# 02_Driver.net
KiCad netlist of a schematic drawn in Altium Designer
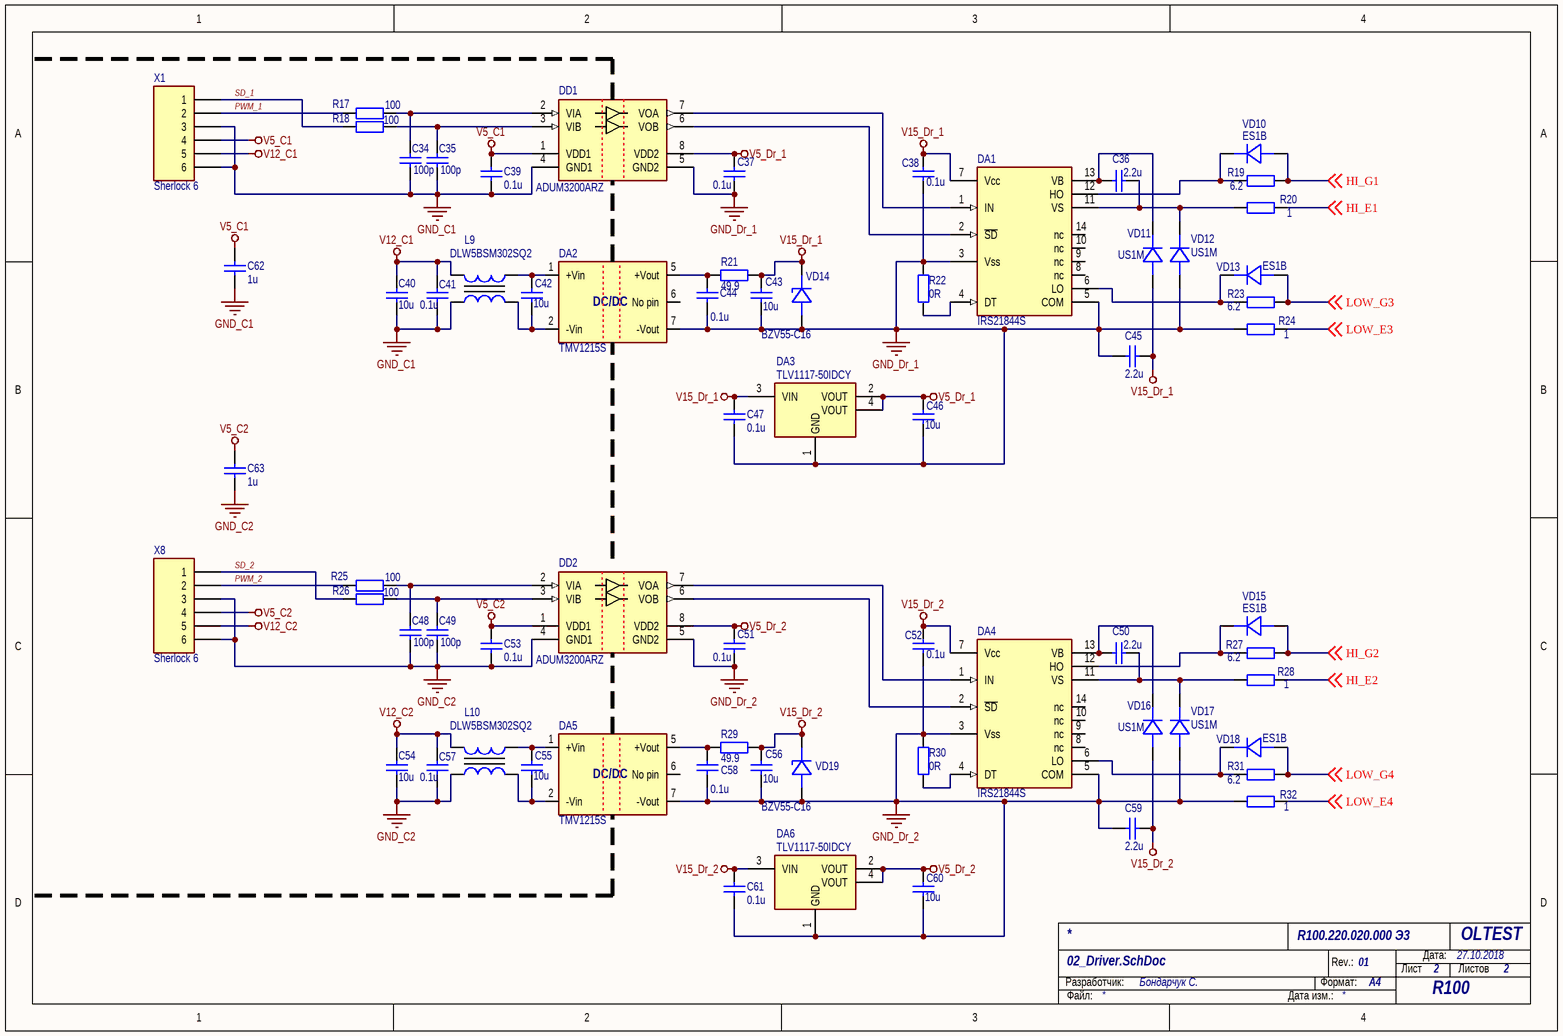
[diagram p0: 02_Driver.SchDoc]

(export (version "E")
  (design (tool "Eeschema 10.0.6"))
  (components
    (comp (ref "C34")
      (value "100p")
      (footprint "mainLib:SMD_C_0603")
      (description "SMD C 0603 MURATA 100V 5% NP0")
      (fields (field (name "PARTNUMBER") "GRM1885C2A101JA01") (field (name "MANUFACTURER") "MURATA"))
      (libsource (lib "mainRCLib") (part "C0603 100p 100V 5%"))
    )
    (comp (ref "C35")
      (value "100p")
      (footprint "mainLib:SMD_C_0603")
      (description "SMD C 0603 MURATA 100V 5% NP0")
      (fields (field (name "PARTNUMBER") "GRM1885C2A101JA01") (field (name "MANUFACTURER") "MURATA"))
      (libsource (lib "mainRCLib") (part "C0603 100p 100V 5%"))
    )
    (comp (ref "C36")
      (value "2.2u")
      (footprint "mainLib:SMD_C_1210")
      (description "SMD C 1210 MURATA 100V 10% X7R")
      (fields (field (name "PARTNUMBER") "GRM32ER72A225KA35L") (field (name "MANUFACTURER") "MURATA"))
      (libsource (lib "mainRCLib") (part "C1210 2.2u 100V 10%"))
    )
    (comp (ref "C37")
      (value "0.1u")
      (footprint "mainLib:SMD_C_0603")
      (description "SMD C 0603 MURATA 50V 10% X7R")
      (fields (field (name "PARTNUMBER") "GRM188R71H104K") (field (name "MANUFACTURER") "MURATA"))
      (libsource (lib "mainRCLib") (part "C0603 0.1u 50V 10%"))
    )
    (comp (ref "C38")
      (value "0.1u")
      (footprint "mainLib:SMD_C_0603")
      (description "SMD C 0603 MURATA 50V 10% X7R")
      (fields (field (name "PARTNUMBER") "GRM188R71H104K") (field (name "MANUFACTURER") "MURATA"))
      (libsource (lib "mainRCLib") (part "C0603 0.1u 50V 10%"))
    )
    (comp (ref "C39")
      (value "0.1u")
      (footprint "mainLib:SMD_C_0603")
      (description "SMD C 0603 MURATA 50V 10% X7R")
      (fields (field (name "PARTNUMBER") "GRM188R71H104K") (field (name "MANUFACTURER") "MURATA"))
      (libsource (lib "mainRCLib") (part "C0603 0.1u 50V 10%"))
    )
    (comp (ref "C40")
      (value "10u")
      (footprint "mainLib:SMD_C_1206")
      (description "SMD C 1206 MURATA 25V 20% X5R")
      (fields (field (name "PARTNUMBER") "GRM31MR61E106M") (field (name "MANUFACTURER") "MURATA"))
      (libsource (lib "mainRCLib") (part "C1206 10u 25V 20%"))
    )
    (comp (ref "C41")
      (value "0.1u")
      (footprint "mainLib:SMD_C_0603")
      (description "SMD C 0603 MURATA 50V 10% X7R")
      (fields (field (name "PARTNUMBER") "GRM188R71H104K") (field (name "MANUFACTURER") "MURATA"))
      (libsource (lib "mainRCLib") (part "C0603 0.1u 50V 10%"))
    )
    (comp (ref "C42")
      (value "10u")
      (footprint "mainLib:SMD_C_1206")
      (description "SMD C 1206 MURATA 25V 20% X5R")
      (fields (field (name "PARTNUMBER") "GRM31MR61E106M") (field (name "MANUFACTURER") "MURATA"))
      (libsource (lib "mainRCLib") (part "C1206 10u 25V 20%"))
    )
    (comp (ref "C43")
      (value "10u")
      (footprint "mainLib:SMD_C_1206")
      (description "SMD C 1206 MURATA 25V 20% X5R")
      (fields (field (name "PARTNUMBER") "GRM31MR61E106M") (field (name "MANUFACTURER") "MURATA"))
      (libsource (lib "mainRCLib") (part "C1206 10u 25V 20%"))
    )
    (comp (ref "C44")
      (value "0.1u")
      (footprint "mainLib:SMD_C_0603")
      (description "SMD C 0603 MURATA 50V 10% X7R")
      (fields (field (name "PARTNUMBER") "GRM188R71H104K") (field (name "MANUFACTURER") "MURATA"))
      (libsource (lib "mainRCLib") (part "C0603 0.1u 50V 10%"))
    )
    (comp (ref "C45")
      (value "2.2u")
      (footprint "mainLib:SMD_C_1210")
      (description "SMD C 1210 MURATA 100V 10% X7R")
      (fields (field (name "PARTNUMBER") "GRM32ER72A225KA35L") (field (name "MANUFACTURER") "MURATA"))
      (libsource (lib "mainRCLib") (part "C1210 2.2u 100V 10%"))
    )
    (comp (ref "C46")
      (value "10u")
      (footprint "mainLib:SMD_C_1206")
      (description "SMD C 1206 MURATA 25V 20% X5R")
      (fields (field (name "PARTNUMBER") "GRM31MR61E106M") (field (name "MANUFACTURER") "MURATA"))
      (libsource (lib "mainRCLib") (part "C1206 10u 25V 20%"))
    )
    (comp (ref "C47")
      (value "0.1u")
      (footprint "mainLib:SMD_C_0603")
      (description "SMD C 0603 MURATA 50V 10% X7R")
      (fields (field (name "PARTNUMBER") "GRM188R71H104K") (field (name "MANUFACTURER") "MURATA"))
      (libsource (lib "mainRCLib") (part "C0603 0.1u 50V 10%"))
    )
    (comp (ref "C48")
      (value "100p")
      (footprint "mainLib:SMD_C_0603")
      (description "SMD C 0603 MURATA 100V 5% NP0")
      (fields (field (name "PARTNUMBER") "GRM1885C2A101JA01") (field (name "MANUFACTURER") "MURATA"))
      (libsource (lib "mainRCLib") (part "C0603 100p 100V 5%"))
    )
    (comp (ref "C49")
      (value "100p")
      (footprint "mainLib:SMD_C_0603")
      (description "SMD C 0603 MURATA 100V 5% NP0")
      (fields (field (name "PARTNUMBER") "GRM1885C2A101JA01") (field (name "MANUFACTURER") "MURATA"))
      (libsource (lib "mainRCLib") (part "C0603 100p 100V 5%"))
    )
    (comp (ref "C50")
      (value "2.2u")
      (footprint "mainLib:SMD_C_1210")
      (description "SMD C 1210 MURATA 100V 10% X7R")
      (fields (field (name "PARTNUMBER") "GRM32ER72A225KA35L") (field (name "MANUFACTURER") "MURATA"))
      (libsource (lib "mainRCLib") (part "C1210 2.2u 100V 10%"))
    )
    (comp (ref "C51")
      (value "0.1u")
      (footprint "mainLib:SMD_C_0603")
      (description "SMD C 0603 MURATA 50V 10% X7R")
      (fields (field (name "PARTNUMBER") "GRM188R71H104K") (field (name "MANUFACTURER") "MURATA"))
      (libsource (lib "mainRCLib") (part "C0603 0.1u 50V 10%"))
    )
    (comp (ref "C52")
      (value "0.1u")
      (footprint "mainLib:SMD_C_0603")
      (description "SMD C 0603 MURATA 50V 10% X7R")
      (fields (field (name "PARTNUMBER") "GRM188R71H104K") (field (name "MANUFACTURER") "MURATA"))
      (libsource (lib "mainRCLib") (part "C0603 0.1u 50V 10%"))
    )
    (comp (ref "C53")
      (value "0.1u")
      (footprint "mainLib:SMD_C_0603")
      (description "SMD C 0603 MURATA 50V 10% X7R")
      (fields (field (name "PARTNUMBER") "GRM188R71H104K") (field (name "MANUFACTURER") "MURATA"))
      (libsource (lib "mainRCLib") (part "C0603 0.1u 50V 10%"))
    )
    (comp (ref "C54")
      (value "10u")
      (footprint "mainLib:SMD_C_1206")
      (description "SMD C 1206 MURATA 25V 20% X5R")
      (fields (field (name "PARTNUMBER") "GRM31MR61E106M") (field (name "MANUFACTURER") "MURATA"))
      (libsource (lib "mainRCLib") (part "C1206 10u 25V 20%"))
    )
    (comp (ref "C55")
      (value "10u")
      (footprint "mainLib:SMD_C_1206")
      (description "SMD C 1206 MURATA 25V 20% X5R")
      (fields (field (name "PARTNUMBER") "GRM31MR61E106M") (field (name "MANUFACTURER") "MURATA"))
      (libsource (lib "mainRCLib") (part "C1206 10u 25V 20%"))
    )
    (comp (ref "C56")
      (value "10u")
      (footprint "mainLib:SMD_C_1206")
      (description "SMD C 1206 MURATA 25V 20% X5R")
      (fields (field (name "PARTNUMBER") "GRM31MR61E106M") (field (name "MANUFACTURER") "MURATA"))
      (libsource (lib "mainRCLib") (part "C1206 10u 25V 20%"))
    )
    (comp (ref "C57")
      (value "0.1u")
      (footprint "mainLib:SMD_C_0603")
      (description "SMD C 0603 MURATA 50V 10% X7R")
      (fields (field (name "PARTNUMBER") "GRM188R71H104K") (field (name "MANUFACTURER") "MURATA"))
      (libsource (lib "mainRCLib") (part "C0603 0.1u 50V 10%"))
    )
    (comp (ref "C58")
      (value "0.1u")
      (footprint "mainLib:SMD_C_0603")
      (description "SMD C 0603 MURATA 50V 10% X7R")
      (fields (field (name "PARTNUMBER") "GRM188R71H104K") (field (name "MANUFACTURER") "MURATA"))
      (libsource (lib "mainRCLib") (part "C0603 0.1u 50V 10%"))
    )
    (comp (ref "C59")
      (value "2.2u")
      (footprint "mainLib:SMD_C_1210")
      (description "SMD C 1210 MURATA 100V 10% X7R")
      (fields (field (name "PARTNUMBER") "GRM32ER72A225KA35L") (field (name "MANUFACTURER") "MURATA"))
      (libsource (lib "mainRCLib") (part "C1210 2.2u 100V 10%"))
    )
    (comp (ref "C60")
      (value "10u")
      (footprint "mainLib:SMD_C_1206")
      (description "SMD C 1206 MURATA 25V 20% X5R")
      (fields (field (name "PARTNUMBER") "GRM31MR61E106M") (field (name "MANUFACTURER") "MURATA"))
      (libsource (lib "mainRCLib") (part "C1206 10u 25V 20%"))
    )
    (comp (ref "C61")
      (value "0.1u")
      (footprint "mainLib:SMD_C_0603")
      (description "SMD C 0603 MURATA 50V 10% X7R")
      (fields (field (name "PARTNUMBER") "GRM188R71H104K") (field (name "MANUFACTURER") "MURATA"))
      (libsource (lib "mainRCLib") (part "C0603 0.1u 50V 10%"))
    )
    (comp (ref "C62")
      (value "1u")
      (footprint "mainLib:SMD_C_0603")
      (description "SMD C 0603 MURATA 25V 10% X7R")
      (fields (field (name "PARTNUMBER") "GRM188R71E105KA12") (field (name "MANUFACTURER") "MURATA"))
      (libsource (lib "mainRCLib") (part "C0603 1uF 25V 10%"))
    )
    (comp (ref "C63")
      (value "1u")
      (footprint "mainLib:SMD_C_0603")
      (description "SMD C 0603 MURATA 25V 10% X7R")
      (fields (field (name "PARTNUMBER") "GRM188R71E105KA12") (field (name "MANUFACTURER") "MURATA"))
      (libsource (lib "mainRCLib") (part "C0603 1uF 25V 10%"))
    )
    (comp (ref "DA1")
      (value "IRS21844S")
      (footprint "mainLib:SOIC-14(127P600X175)")
      (description "Half-Bridge Driver")
      (fields
        (field (name "MANUFACTURER") "International Rectifier")
        (field (name "PARTNUMBER") "IRS21844SPBF")
      )
      (libsource (lib "mainLib") (part "IRS21844S"))
    )
    (comp (ref "DA2")
      (value "TMV1215S")
      (footprint "mainLib:SIP7")
      (description "DC/DC")
      (fields (field (name "MANUFACTURER") "TRACO POWER"))
      (libsource (lib "mainLib") (part "TMV1215S"))
    )
    (comp (ref "DA3")
      (value "TLV1117-50IDCY")
      (footprint "mainLib:SOT-223_M")
      (description "Voltage regulator 5.0V 800mA")
      (fields (field (name "MANUFACTURER") "Texas Instrument"))
      (libsource (lib "mainLib") (part "TLV1117-50IDCY"))
    )
    (comp (ref "DA4")
      (value "IRS21844S")
      (footprint "mainLib:SOIC-14(127P600X175)")
      (description "Half-Bridge Driver")
      (fields
        (field (name "MANUFACTURER") "International Rectifier")
        (field (name "PARTNUMBER") "IRS21844SPBF")
      )
      (libsource (lib "mainLib") (part "IRS21844S"))
    )
    (comp (ref "DA5")
      (value "TMV1215S")
      (footprint "mainLib:SIP7")
      (description "DC/DC")
      (fields (field (name "MANUFACTURER") "TRACO POWER"))
      (libsource (lib "mainLib") (part "TMV1215S"))
    )
    (comp (ref "DA6")
      (value "TLV1117-50IDCY")
      (footprint "mainLib:SOT-223_M")
      (description "Voltage regulator 5.0V 800mA")
      (fields (field (name "MANUFACTURER") "Texas Instrument"))
      (libsource (lib "mainLib") (part "TLV1117-50IDCY"))
    )
    (comp (ref "DD1")
      (value "ADUM3200ARZ")
      (footprint "mainLib:SOIC-8")
      (fields (field (name "MANUFACTURER") "Analog Devices"))
      (libsource (lib "mainLib") (part "ADUM3200ARZ"))
    )
    (comp (ref "DD2")
      (value "ADUM3200ARZ")
      (footprint "mainLib:SOIC-8")
      (fields (field (name "MANUFACTURER") "Analog Devices"))
      (libsource (lib "mainLib") (part "ADUM3200ARZ"))
    )
    (comp (ref "L9")
      (value "DLW5BSM302SQ2")
      (footprint "mainLib:DLW5BS(AH)")
      (description "SMD Common Mode Choke Coil 0.5A Z = 3000 Ohm / 100 MHz")
      (fields (field (name "MANUFACTURER") "MURATA"))
      (libsource (lib "mainLib") (part "DLW5BSM302SQ2"))
    )
    (comp (ref "L10")
      (value "DLW5BSM302SQ2")
      (footprint "mainLib:DLW5BS(AH)")
      (description "SMD Common Mode Choke Coil 0.5A Z = 3000 Ohm / 100 MHz")
      (fields (field (name "MANUFACTURER") "MURATA"))
      (libsource (lib "mainLib") (part "DLW5BSM302SQ2"))
    )
    (comp (ref "R17")
      (value "100")
      (footprint "SMD_R_0603")
      (description "SMD R 0603 VISHAY 0.1W 75V 1% 100ppm")
      (fields (field (name "PARTNUMBER") "CRCW0603100RFK") (field (name "MANUFACTURER") "VISHAY"))
      (libsource (lib "mainRCLib") (part "R0603 100 1%"))
    )
    (comp (ref "R18")
      (value "100")
      (footprint "SMD_R_0603")
      (description "SMD R 0603 VISHAY 0.1W 75V 1% 100ppm")
      (fields (field (name "PARTNUMBER") "CRCW0603100RFK") (field (name "MANUFACTURER") "VISHAY"))
      (libsource (lib "mainRCLib") (part "R0603 100 1%"))
    )
    (comp (ref "R19")
      (value "6.2")
      (footprint "mainLib:SMD_R_1206")
      (description "SMD R 1206 VISHAY 0.25W 200V 1% 100ppm")
      (fields (field (name "PARTNUMBER") "CRCW12066R20FK") (field (name "MANUFACTURER") "VISHAY"))
      (libsource (lib "mainRCLib") (part "R1206 6.2 1%"))
    )
    (comp (ref "R20")
      (value "1")
      (footprint "mainLib:SMD_R_1206")
      (description "SMD R 1206 VISHAY 0.25W 200V 1% 100ppm")
      (fields (field (name "PARTNUMBER") "CRCW12061R00FK") (field (name "MANUFACTURER") "VISHAY"))
      (libsource (lib "mainRCLib") (part "R1206 1 1%"))
    )
    (comp (ref "R21")
      (value "49.9")
      (footprint "mainLib:SMD_R_0805")
      (description "SMD R 0805 VISHAY 0.125W 150V 1% 100ppm")
      (fields (field (name "PARTNUMBER") "CRCW080549R9FK") (field (name "MANUFACTURER") "VISHAY"))
      (libsource (lib "mainRCLib") (part "R0805 49.9 1%"))
    )
    (comp (ref "R22")
      (value "0R")
      (footprint "mainLib:SMD_R_0603")
      (description "SMD R 0603 VISHAY 0.1W 75V 1% 100ppm")
      (fields (field (name "PARTNUMBER") "CRCW06030000Z0") (field (name "MANUFACTURER") "VISHAY"))
      (libsource (lib "mainRCLib") (part "R0603 0R 1%"))
    )
    (comp (ref "R23")
      (value "6.2")
      (footprint "mainLib:SMD_R_1206")
      (description "SMD R 1206 VISHAY 0.25W 200V 1% 100ppm")
      (fields (field (name "PARTNUMBER") "CRCW12066R20FK") (field (name "MANUFACTURER") "VISHAY"))
      (libsource (lib "mainRCLib") (part "R1206 6.2 1%"))
    )
    (comp (ref "R24")
      (value "1")
      (footprint "mainLib:SMD_R_1206")
      (description "SMD R 1206 VISHAY 0.25W 200V 1% 100ppm")
      (fields (field (name "PARTNUMBER") "CRCW12061R00FK") (field (name "MANUFACTURER") "VISHAY"))
      (libsource (lib "mainRCLib") (part "R1206 1 1%"))
    )
    (comp (ref "R25")
      (value "100")
      (footprint "SMD_R_0603")
      (description "SMD R 0603 VISHAY 0.1W 75V 1% 100ppm")
      (fields (field (name "PARTNUMBER") "CRCW0603100RFK") (field (name "MANUFACTURER") "VISHAY"))
      (libsource (lib "mainRCLib") (part "R0603 100 1%"))
    )
    (comp (ref "R26")
      (value "100")
      (footprint "SMD_R_0603")
      (description "SMD R 0603 VISHAY 0.1W 75V 1% 100ppm")
      (fields (field (name "PARTNUMBER") "CRCW0603100RFK") (field (name "MANUFACTURER") "VISHAY"))
      (libsource (lib "mainRCLib") (part "R0603 100 1%"))
    )
    (comp (ref "R27")
      (value "6.2")
      (footprint "mainLib:SMD_R_1206")
      (description "SMD R 1206 VISHAY 0.25W 200V 1% 100ppm")
      (fields (field (name "PARTNUMBER") "CRCW12066R20FK") (field (name "MANUFACTURER") "VISHAY"))
      (libsource (lib "mainRCLib") (part "R1206 6.2 1%"))
    )
    (comp (ref "R28")
      (value "1")
      (footprint "mainLib:SMD_R_1206")
      (description "SMD R 1206 VISHAY 0.25W 200V 1% 100ppm")
      (fields (field (name "PARTNUMBER") "CRCW12061R00FK") (field (name "MANUFACTURER") "VISHAY"))
      (libsource (lib "mainRCLib") (part "R1206 1 1%"))
    )
    (comp (ref "R29")
      (value "49.9")
      (footprint "mainLib:SMD_R_0805")
      (description "SMD R 0805 VISHAY 0.125W 150V 1% 100ppm")
      (fields (field (name "PARTNUMBER") "CRCW080549R9FK") (field (name "MANUFACTURER") "VISHAY"))
      (libsource (lib "mainRCLib") (part "R0805 49.9 1%"))
    )
    (comp (ref "R30")
      (value "0R")
      (footprint "mainLib:SMD_R_0603")
      (description "SMD R 0603 VISHAY 0.1W 75V 1% 100ppm")
      (fields (field (name "PARTNUMBER") "CRCW06030000Z0") (field (name "MANUFACTURER") "VISHAY"))
      (libsource (lib "mainRCLib") (part "R0603 0R 1%"))
    )
    (comp (ref "R31")
      (value "6.2")
      (footprint "mainLib:SMD_R_1206")
      (description "SMD R 1206 VISHAY 0.25W 200V 1% 100ppm")
      (fields (field (name "PARTNUMBER") "CRCW12066R20FK") (field (name "MANUFACTURER") "VISHAY"))
      (libsource (lib "mainRCLib") (part "R1206 6.2 1%"))
    )
    (comp (ref "R32")
      (value "1")
      (footprint "mainLib:SMD_R_1206")
      (description "SMD R 1206 VISHAY 0.25W 200V 1% 100ppm")
      (fields (field (name "PARTNUMBER") "CRCW12061R00FK") (field (name "MANUFACTURER") "VISHAY"))
      (libsource (lib "mainRCLib") (part "R1206 1 1%"))
    )
    (comp (ref "VD10")
      (value "ES1B")
      (footprint "mainLib:DO-214AC")
      (description "Vr=100V If=1A Ultrafast")
      (fields (field (name "MANUFACTURER") "Vishay"))
      (libsource (lib "mainLib") (part "ES1B"))
    )
    (comp (ref "VD11")
      (value "US1M")
      (footprint "mainLib:DO-214AC")
      (description "Vr=1000V If=1A Ultrafast")
      (fields (field (name "MANUFACTURER") "Vishay"))
      (libsource (lib "mainLib") (part "US1M"))
    )
    (comp (ref "VD12")
      (value "US1M")
      (footprint "mainLib:DO-214AC")
      (description "Vr=1000V If=1A Ultrafast")
      (fields (field (name "MANUFACTURER") "Vishay"))
      (libsource (lib "mainLib") (part "US1M"))
    )
    (comp (ref "VD13")
      (value "ES1B")
      (footprint "mainLib:DO-214AC")
      (description "Vr=100V If=1A Ultrafast")
      (fields (field (name "MANUFACTURER") "Vishay"))
      (libsource (lib "mainLib") (part "ES1B"))
    )
    (comp (ref "VD14")
      (value "BZV55-C16")
      (footprint "mainLib:SOD80C")
      (description "0.5W Vz=16V +-5%")
      (fields (field (name "MANUFACTURER") "NXP"))
      (libsource (lib "mainLib") (part "BZV55-C16"))
    )
    (comp (ref "VD15")
      (value "ES1B")
      (footprint "mainLib:DO-214AC")
      (description "Vr=100V If=1A Ultrafast")
      (fields (field (name "MANUFACTURER") "Vishay"))
      (libsource (lib "mainLib") (part "ES1B"))
    )
    (comp (ref "VD16")
      (value "US1M")
      (footprint "mainLib:DO-214AC")
      (description "Vr=1000V If=1A Ultrafast")
      (fields (field (name "MANUFACTURER") "Vishay"))
      (libsource (lib "mainLib") (part "US1M"))
    )
    (comp (ref "VD17")
      (value "US1M")
      (footprint "mainLib:DO-214AC")
      (description "Vr=1000V If=1A Ultrafast")
      (fields (field (name "MANUFACTURER") "Vishay"))
      (libsource (lib "mainLib") (part "US1M"))
    )
    (comp (ref "VD18")
      (value "ES1B")
      (footprint "mainLib:DO-214AC")
      (description "Vr=100V If=1A Ultrafast")
      (fields (field (name "MANUFACTURER") "Vishay"))
      (libsource (lib "mainLib") (part "ES1B"))
    )
    (comp (ref "VD19")
      (value "BZV55-C16")
      (footprint "mainLib:SOD80C")
      (description "0.5W Vz=16V +-5%")
      (fields (field (name "MANUFACTURER") "NXP"))
      (libsource (lib "mainLib") (part "BZV55-C16"))
    )
    (comp (ref "X1")
      (value "Sherlock 6")
      (footprint "mainLib:35362-0650")
      (description "Sherlock 6 Side, 2A 125V 2mm")
      (fields (field (name "PARTNUMBER") "35362-0650") (field (name "MANUFACTURER") "MOLEX"))
      (libsource (lib "mainLib") (part "35363-0650"))
    )
    (comp (ref "X8")
      (value "Sherlock 6")
      (footprint "mainLib:35362-0650")
      (description "Sherlock 6 Side, 2A 125V 2mm")
      (fields (field (name "PARTNUMBER") "35362-0650") (field (name "MANUFACTURER") "MOLEX"))
      (libsource (lib "mainLib") (part "35363-0650"))
    )
  )
  (nets
    (net (code "1") (name "/PWM_1") (class "Default")
      (node (ref "R17") (pin "1") (pinfunction "1_1") (pintype "passive"))
      (node (ref "X1") (pin "2") (pinfunction "2_2") (pintype "passive"))
    )
    (net (code "2") (name "/PWM_2") (class "Default")
      (node (ref "R25") (pin "1") (pinfunction "1_1") (pintype "passive"))
      (node (ref "X8") (pin "2") (pinfunction "2_2") (pintype "passive"))
    )
    (net (code "3") (name "/SD_1") (class "Default")
      (node (ref "R18") (pin "1") (pinfunction "1_1") (pintype "passive"))
      (node (ref "X1") (pin "1") (pinfunction "1_1") (pintype "passive"))
    )
    (net (code "4") (name "/SD_2") (class "Default")
      (node (ref "R26") (pin "1") (pinfunction "1_1") (pintype "passive"))
      (node (ref "X8") (pin "1") (pinfunction "1_1") (pintype "passive"))
    )
    (net (code "5") (name "GND_C1") (class "Default")
      (node (ref "C34") (pin "2") (pinfunction "2_2") (pintype "passive"))
      (node (ref "C35") (pin "2") (pinfunction "2_2") (pintype "passive"))
      (node (ref "C39") (pin "1") (pinfunction "1_1") (pintype "passive"))
      (node (ref "C40") (pin "1") (pinfunction "1_1") (pintype "passive"))
      (node (ref "C41") (pin "1") (pinfunction "1_1") (pintype "passive"))
      (node (ref "C62") (pin "2") (pinfunction "2_2") (pintype "passive"))
      (node (ref "DD1") (pin "4") (pinfunction "GND1_4") (pintype "power_in"))
      (node (ref "L9") (pin "4") (pinfunction "4_4") (pintype "passive"))
      (node (ref "X1") (pin "3") (pinfunction "3_3") (pintype "passive"))
      (node (ref "X1") (pin "6") (pinfunction "6_6") (pintype "passive"))
    )
    (net (code "6") (name "GND_C2") (class "Default")
      (node (ref "C48") (pin "2") (pinfunction "2_2") (pintype "passive"))
      (node (ref "C49") (pin "2") (pinfunction "2_2") (pintype "passive"))
      (node (ref "C53") (pin "1") (pinfunction "1_1") (pintype "passive"))
      (node (ref "C54") (pin "1") (pinfunction "1_1") (pintype "passive"))
      (node (ref "C57") (pin "1") (pinfunction "1_1") (pintype "passive"))
      (node (ref "C63") (pin "2") (pinfunction "2_2") (pintype "passive"))
      (node (ref "DD2") (pin "4") (pinfunction "GND1_4") (pintype "power_in"))
      (node (ref "L10") (pin "4") (pinfunction "4_4") (pintype "passive"))
      (node (ref "X8") (pin "3") (pinfunction "3_3") (pintype "passive"))
      (node (ref "X8") (pin "6") (pinfunction "6_6") (pintype "passive"))
    )
    (net (code "7") (name "GND_Dr_1") (class "Default")
      (node (ref "C37") (pin "1") (pinfunction "1_1") (pintype "passive"))
      (node (ref "C38") (pin "2") (pinfunction "2_2") (pintype "passive"))
      (node (ref "C43") (pin "1") (pinfunction "1_1") (pintype "passive"))
      (node (ref "C44") (pin "1") (pinfunction "1_1") (pintype "passive"))
      (node (ref "C45") (pin "2") (pinfunction "2_2") (pintype "passive"))
      (node (ref "C46") (pin "1") (pinfunction "1_1") (pintype "passive"))
      (node (ref "C47") (pin "1") (pinfunction "1_1") (pintype "passive"))
      (node (ref "DA1") (pin "3") (pinfunction "Vss_3") (pintype "power_in"))
      (node (ref "DA1") (pin "5") (pinfunction "COM_5") (pintype "power_in"))
      (node (ref "DA2") (pin "7") (pinfunction "-Vout_7") (pintype "passive"))
      (node (ref "DA3") (pin "1") (pinfunction "GND_1") (pintype "power_in"))
      (node (ref "DD1") (pin "5") (pinfunction "GND2_5") (pintype "power_in"))
      (node (ref "R22") (pin "1") (pinfunction "1_1") (pintype "passive"))
      (node (ref "R24") (pin "1") (pinfunction "1_1") (pintype "passive"))
      (node (ref "VD12") (pin "1") (pinfunction "ANODE_1") (pintype "passive"))
      (node (ref "VD14") (pin "1") (pinfunction "ANODE_1") (pintype "passive"))
    )
    (net (code "8") (name "GND_Dr_2") (class "Default")
      (node (ref "C51") (pin "1") (pinfunction "1_1") (pintype "passive"))
      (node (ref "C52") (pin "2") (pinfunction "2_2") (pintype "passive"))
      (node (ref "C56") (pin "1") (pinfunction "1_1") (pintype "passive"))
      (node (ref "C58") (pin "1") (pinfunction "1_1") (pintype "passive"))
      (node (ref "C59") (pin "2") (pinfunction "2_2") (pintype "passive"))
      (node (ref "C60") (pin "1") (pinfunction "1_1") (pintype "passive"))
      (node (ref "C61") (pin "1") (pinfunction "1_1") (pintype "passive"))
      (node (ref "DA4") (pin "3") (pinfunction "Vss_3") (pintype "power_in"))
      (node (ref "DA4") (pin "5") (pinfunction "COM_5") (pintype "power_in"))
      (node (ref "DA5") (pin "7") (pinfunction "-Vout_7") (pintype "passive"))
      (node (ref "DA6") (pin "1") (pinfunction "GND_1") (pintype "power_in"))
      (node (ref "DD2") (pin "5") (pinfunction "GND2_5") (pintype "power_in"))
      (node (ref "R30") (pin "1") (pinfunction "1_1") (pintype "passive"))
      (node (ref "R32") (pin "1") (pinfunction "1_1") (pintype "passive"))
      (node (ref "VD17") (pin "1") (pinfunction "ANODE_1") (pintype "passive"))
      (node (ref "VD19") (pin "1") (pinfunction "ANODE_1") (pintype "passive"))
    )
    (net (code "9") (name "HI_E1") (class "Default")
      (node (ref "R20") (pin "2") (pinfunction "2_2") (pintype "passive"))
    )
    (net (code "10") (name "HI_E2") (class "Default")
      (node (ref "R28") (pin "2") (pinfunction "2_2") (pintype "passive"))
    )
    (net (code "11") (name "HI_G1") (class "Default")
      (node (ref "R19") (pin "2") (pinfunction "2_2") (pintype "passive"))
      (node (ref "VD10") (pin "1") (pinfunction "ANODE_1") (pintype "passive"))
    )
    (net (code "12") (name "HI_G2") (class "Default")
      (node (ref "R27") (pin "2") (pinfunction "2_2") (pintype "passive"))
      (node (ref "VD15") (pin "1") (pinfunction "ANODE_1") (pintype "passive"))
    )
    (net (code "13") (name "LOW_E3") (class "Default")
      (node (ref "R24") (pin "2") (pinfunction "2_2") (pintype "passive"))
    )
    (net (code "14") (name "LOW_E4") (class "Default")
      (node (ref "R32") (pin "2") (pinfunction "2_2") (pintype "passive"))
    )
    (net (code "15") (name "LOW_G3") (class "Default")
      (node (ref "R23") (pin "2") (pinfunction "2_2") (pintype "passive"))
      (node (ref "VD13") (pin "1") (pinfunction "ANODE_1") (pintype "passive"))
    )
    (net (code "16") (name "LOW_G4") (class "Default")
      (node (ref "R31") (pin "2") (pinfunction "2_2") (pintype "passive"))
      (node (ref "VD18") (pin "1") (pinfunction "ANODE_1") (pintype "passive"))
    )
    (net (code "17") (name "Net-(DA1-DT)") (class "Default")
      (node (ref "DA1") (pin "4") (pinfunction "DT_4") (pintype "input"))
      (node (ref "R22") (pin "2") (pinfunction "2_2") (pintype "passive"))
    )
    (net (code "18") (name "Net-(DA1-HO)") (class "Default")
      (node (ref "DA1") (pin "12") (pinfunction "HO_12") (pintype "passive"))
      (node (ref "R19") (pin "1") (pinfunction "1_1") (pintype "passive"))
      (node (ref "VD10") (pin "2") (pinfunction "CATHODE_2") (pintype "passive"))
    )
    (net (code "19") (name "Net-(DA1-IN)") (class "Default")
      (node (ref "DA1") (pin "1") (pinfunction "IN_1") (pintype "input"))
      (node (ref "DD1") (pin "7") (pinfunction "VOA_7") (pintype "output"))
    )
    (net (code "20") (name "Net-(DA1-LO)") (class "Default")
      (node (ref "DA1") (pin "6") (pinfunction "LO_6") (pintype "passive"))
      (node (ref "R23") (pin "1") (pinfunction "1_1") (pintype "passive"))
      (node (ref "VD13") (pin "2") (pinfunction "CATHODE_2") (pintype "passive"))
    )
    (net (code "21") (name "Net-(DA1-VB)") (class "Default")
      (node (ref "C36") (pin "1") (pinfunction "1_1") (pintype "passive"))
      (node (ref "DA1") (pin "13") (pinfunction "VB_13") (pintype "passive"))
      (node (ref "VD11") (pin "2") (pinfunction "CATHODE_2") (pintype "passive"))
    )
    (net (code "22") (name "Net-(DA1-VS)") (class "Default")
      (node (ref "C36") (pin "2") (pinfunction "2_2") (pintype "passive"))
      (node (ref "DA1") (pin "11") (pinfunction "VS_11") (pintype "passive"))
      (node (ref "R20") (pin "1") (pinfunction "1_1") (pintype "passive"))
      (node (ref "VD12") (pin "2") (pinfunction "CATHODE_2") (pintype "passive"))
    )
    (net (code "23") (name "Net-(DA1-~{SD})") (class "Default")
      (node (ref "DA1") (pin "2") (pinfunction "~{SD}_2") (pintype "input"))
      (node (ref "DD1") (pin "6") (pinfunction "VOB_6") (pintype "output"))
    )
    (net (code "24") (name "Net-(DA2-+Vin)") (class "Default")
      (node (ref "C42") (pin "2") (pinfunction "2_2") (pintype "passive"))
      (node (ref "DA2") (pin "1") (pinfunction "+Vin_1") (pintype "passive"))
      (node (ref "L9") (pin "2") (pinfunction "2_2") (pintype "passive"))
    )
    (net (code "25") (name "Net-(DA2-+Vout)") (class "Default")
      (node (ref "C44") (pin "2") (pinfunction "2_2") (pintype "passive"))
      (node (ref "DA2") (pin "5") (pinfunction "+Vout_5") (pintype "passive"))
      (node (ref "R21") (pin "1") (pinfunction "1_1") (pintype "passive"))
    )
    (net (code "26") (name "Net-(DA2--Vin)") (class "Default")
      (node (ref "C42") (pin "1") (pinfunction "1_1") (pintype "passive"))
      (node (ref "DA2") (pin "2") (pinfunction "-Vin_2") (pintype "passive"))
      (node (ref "L9") (pin "3") (pinfunction "3_3") (pintype "passive"))
    )
    (net (code "27") (name "Net-(DA4-DT)") (class "Default")
      (node (ref "DA4") (pin "4") (pinfunction "DT_4") (pintype "input"))
      (node (ref "R30") (pin "2") (pinfunction "2_2") (pintype "passive"))
    )
    (net (code "28") (name "Net-(DA4-HO)") (class "Default")
      (node (ref "DA4") (pin "12") (pinfunction "HO_12") (pintype "passive"))
      (node (ref "R27") (pin "1") (pinfunction "1_1") (pintype "passive"))
      (node (ref "VD15") (pin "2") (pinfunction "CATHODE_2") (pintype "passive"))
    )
    (net (code "29") (name "Net-(DA4-IN)") (class "Default")
      (node (ref "DA4") (pin "1") (pinfunction "IN_1") (pintype "input"))
      (node (ref "DD2") (pin "7") (pinfunction "VOA_7") (pintype "output"))
    )
    (net (code "30") (name "Net-(DA4-LO)") (class "Default")
      (node (ref "DA4") (pin "6") (pinfunction "LO_6") (pintype "passive"))
      (node (ref "R31") (pin "1") (pinfunction "1_1") (pintype "passive"))
      (node (ref "VD18") (pin "2") (pinfunction "CATHODE_2") (pintype "passive"))
    )
    (net (code "31") (name "Net-(DA4-VB)") (class "Default")
      (node (ref "C50") (pin "1") (pinfunction "1_1") (pintype "passive"))
      (node (ref "DA4") (pin "13") (pinfunction "VB_13") (pintype "passive"))
      (node (ref "VD16") (pin "2") (pinfunction "CATHODE_2") (pintype "passive"))
    )
    (net (code "32") (name "Net-(DA4-VS)") (class "Default")
      (node (ref "C50") (pin "2") (pinfunction "2_2") (pintype "passive"))
      (node (ref "DA4") (pin "11") (pinfunction "VS_11") (pintype "passive"))
      (node (ref "R28") (pin "1") (pinfunction "1_1") (pintype "passive"))
      (node (ref "VD17") (pin "2") (pinfunction "CATHODE_2") (pintype "passive"))
    )
    (net (code "33") (name "Net-(DA4-~{SD})") (class "Default")
      (node (ref "DA4") (pin "2") (pinfunction "~{SD}_2") (pintype "input"))
      (node (ref "DD2") (pin "6") (pinfunction "VOB_6") (pintype "output"))
    )
    (net (code "34") (name "Net-(DA5-+Vin)") (class "Default")
      (node (ref "C55") (pin "2") (pinfunction "2_2") (pintype "passive"))
      (node (ref "DA5") (pin "1") (pinfunction "+Vin_1") (pintype "passive"))
      (node (ref "L10") (pin "2") (pinfunction "2_2") (pintype "passive"))
    )
    (net (code "35") (name "Net-(DA5-+Vout)") (class "Default")
      (node (ref "C58") (pin "2") (pinfunction "2_2") (pintype "passive"))
      (node (ref "DA5") (pin "5") (pinfunction "+Vout_5") (pintype "passive"))
      (node (ref "R29") (pin "1") (pinfunction "1_1") (pintype "passive"))
    )
    (net (code "36") (name "Net-(DA5--Vin)") (class "Default")
      (node (ref "C55") (pin "1") (pinfunction "1_1") (pintype "passive"))
      (node (ref "DA5") (pin "2") (pinfunction "-Vin_2") (pintype "passive"))
      (node (ref "L10") (pin "3") (pinfunction "3_3") (pintype "passive"))
    )
    (net (code "37") (name "Net-(DD1-VIA)") (class "Default")
      (node (ref "C34") (pin "1") (pinfunction "1_1") (pintype "passive"))
      (node (ref "DD1") (pin "2") (pinfunction "VIA_2") (pintype "input"))
      (node (ref "R17") (pin "2") (pinfunction "2_2") (pintype "passive"))
    )
    (net (code "38") (name "Net-(DD1-VIB)") (class "Default")
      (node (ref "C35") (pin "1") (pinfunction "1_1") (pintype "passive"))
      (node (ref "DD1") (pin "3") (pinfunction "VIB_3") (pintype "input"))
      (node (ref "R18") (pin "2") (pinfunction "2_2") (pintype "passive"))
    )
    (net (code "39") (name "Net-(DD2-VIA)") (class "Default")
      (node (ref "C48") (pin "1") (pinfunction "1_1") (pintype "passive"))
      (node (ref "DD2") (pin "2") (pinfunction "VIA_2") (pintype "input"))
      (node (ref "R25") (pin "2") (pinfunction "2_2") (pintype "passive"))
    )
    (net (code "40") (name "Net-(DD2-VIB)") (class "Default")
      (node (ref "C49") (pin "1") (pinfunction "1_1") (pintype "passive"))
      (node (ref "DD2") (pin "3") (pinfunction "VIB_3") (pintype "input"))
      (node (ref "R26") (pin "2") (pinfunction "2_2") (pintype "passive"))
    )
    (net (code "41") (name "V5_C1") (class "Default")
      (node (ref "C39") (pin "2") (pinfunction "2_2") (pintype "passive"))
      (node (ref "C62") (pin "1") (pinfunction "1_1") (pintype "passive"))
      (node (ref "DD1") (pin "1") (pinfunction "VDD1_1") (pintype "power_in"))
      (node (ref "X1") (pin "4") (pinfunction "4_4") (pintype "passive"))
    )
    (net (code "42") (name "V5_C2") (class "Default")
      (node (ref "C53") (pin "2") (pinfunction "2_2") (pintype "passive"))
      (node (ref "C63") (pin "1") (pinfunction "1_1") (pintype "passive"))
      (node (ref "DD2") (pin "1") (pinfunction "VDD1_1") (pintype "power_in"))
      (node (ref "X8") (pin "4") (pinfunction "4_4") (pintype "passive"))
    )
    (net (code "43") (name "V5_Dr_1") (class "Default")
      (node (ref "C37") (pin "2") (pinfunction "2_2") (pintype "passive"))
      (node (ref "C46") (pin "2") (pinfunction "2_2") (pintype "passive"))
      (node (ref "DA3") (pin "2") (pinfunction "VOUT_2") (pintype "power_in"))
      (node (ref "DA3") (pin "4") (pinfunction "VOUT_4") (pintype "power_in"))
      (node (ref "DD1") (pin "8") (pinfunction "VDD2_8") (pintype "power_in"))
    )
    (net (code "44") (name "V5_Dr_2") (class "Default")
      (node (ref "C51") (pin "2") (pinfunction "2_2") (pintype "passive"))
      (node (ref "C60") (pin "2") (pinfunction "2_2") (pintype "passive"))
      (node (ref "DA6") (pin "2") (pinfunction "VOUT_2") (pintype "power_in"))
      (node (ref "DA6") (pin "4") (pinfunction "VOUT_4") (pintype "power_in"))
      (node (ref "DD2") (pin "8") (pinfunction "VDD2_8") (pintype "power_in"))
    )
    (net (code "45") (name "V12_C1") (class "Default")
      (node (ref "C40") (pin "2") (pinfunction "2_2") (pintype "passive"))
      (node (ref "C41") (pin "2") (pinfunction "2_2") (pintype "passive"))
      (node (ref "L9") (pin "1") (pinfunction "1_1") (pintype "passive"))
      (node (ref "X1") (pin "5") (pinfunction "5_5") (pintype "passive"))
    )
    (net (code "46") (name "V12_C2") (class "Default")
      (node (ref "C54") (pin "2") (pinfunction "2_2") (pintype "passive"))
      (node (ref "C57") (pin "2") (pinfunction "2_2") (pintype "passive"))
      (node (ref "L10") (pin "1") (pinfunction "1_1") (pintype "passive"))
      (node (ref "X8") (pin "5") (pinfunction "5_5") (pintype "passive"))
    )
    (net (code "47") (name "V15_Dr_1") (class "Default")
      (node (ref "C38") (pin "1") (pinfunction "1_1") (pintype "passive"))
      (node (ref "C43") (pin "2") (pinfunction "2_2") (pintype "passive"))
      (node (ref "C45") (pin "1") (pinfunction "1_1") (pintype "passive"))
      (node (ref "C47") (pin "2") (pinfunction "2_2") (pintype "passive"))
      (node (ref "DA1") (pin "7") (pinfunction "Vcc_7") (pintype "power_in"))
      (node (ref "DA3") (pin "3") (pinfunction "VIN_3") (pintype "power_in"))
      (node (ref "R21") (pin "2") (pinfunction "2_2") (pintype "passive"))
      (node (ref "VD11") (pin "1") (pinfunction "ANODE_1") (pintype "passive"))
      (node (ref "VD14") (pin "2") (pinfunction "CATHODE_2") (pintype "passive"))
    )
    (net (code "48") (name "V15_Dr_2") (class "Default")
      (node (ref "C52") (pin "1") (pinfunction "1_1") (pintype "passive"))
      (node (ref "C56") (pin "2") (pinfunction "2_2") (pintype "passive"))
      (node (ref "C59") (pin "1") (pinfunction "1_1") (pintype "passive"))
      (node (ref "C61") (pin "2") (pinfunction "2_2") (pintype "passive"))
      (node (ref "DA4") (pin "7") (pinfunction "Vcc_7") (pintype "power_in"))
      (node (ref "DA6") (pin "3") (pinfunction "VIN_3") (pintype "power_in"))
      (node (ref "R29") (pin "2") (pinfunction "2_2") (pintype "passive"))
      (node (ref "VD16") (pin "1") (pinfunction "ANODE_1") (pintype "passive"))
      (node (ref "VD19") (pin "2") (pinfunction "CATHODE_2") (pintype "passive"))
    )
    (net (code "49") (name "unconnected-(DA1-nc-Pad8)") (class "Default")
      (node (ref "DA1") (pin "8") (pinfunction "nc_8") (pintype "passive"))
    )
    (net (code "50") (name "unconnected-(DA1-nc-Pad9)") (class "Default")
      (node (ref "DA1") (pin "9") (pinfunction "nc_9") (pintype "passive"))
    )
    (net (code "51") (name "unconnected-(DA1-nc-Pad10)") (class "Default")
      (node (ref "DA1") (pin "10") (pinfunction "nc_10") (pintype "passive"))
    )
    (net (code "52") (name "unconnected-(DA1-nc-Pad14)") (class "Default")
      (node (ref "DA1") (pin "14") (pinfunction "nc_14") (pintype "passive"))
    )
    (net (code "53") (name "unconnected-(DA2-No_pin-Pad6)") (class "Default")
      (node (ref "DA2") (pin "6") (pinfunction "No_pin_6") (pintype "passive"))
    )
    (net (code "54") (name "unconnected-(DA4-nc-Pad8)") (class "Default")
      (node (ref "DA4") (pin "8") (pinfunction "nc_8") (pintype "passive"))
    )
    (net (code "55") (name "unconnected-(DA4-nc-Pad9)") (class "Default")
      (node (ref "DA4") (pin "9") (pinfunction "nc_9") (pintype "passive"))
    )
    (net (code "56") (name "unconnected-(DA4-nc-Pad10)") (class "Default")
      (node (ref "DA4") (pin "10") (pinfunction "nc_10") (pintype "passive"))
    )
    (net (code "57") (name "unconnected-(DA4-nc-Pad14)") (class "Default")
      (node (ref "DA4") (pin "14") (pinfunction "nc_14") (pintype "passive"))
    )
    (net (code "58") (name "unconnected-(DA5-No_pin-Pad6)") (class "Default")
      (node (ref "DA5") (pin "6") (pinfunction "No_pin_6") (pintype "passive"))
    )
  )
)
